# schematic.net
KiCad netlist of a schematic drawn in EasyEDA
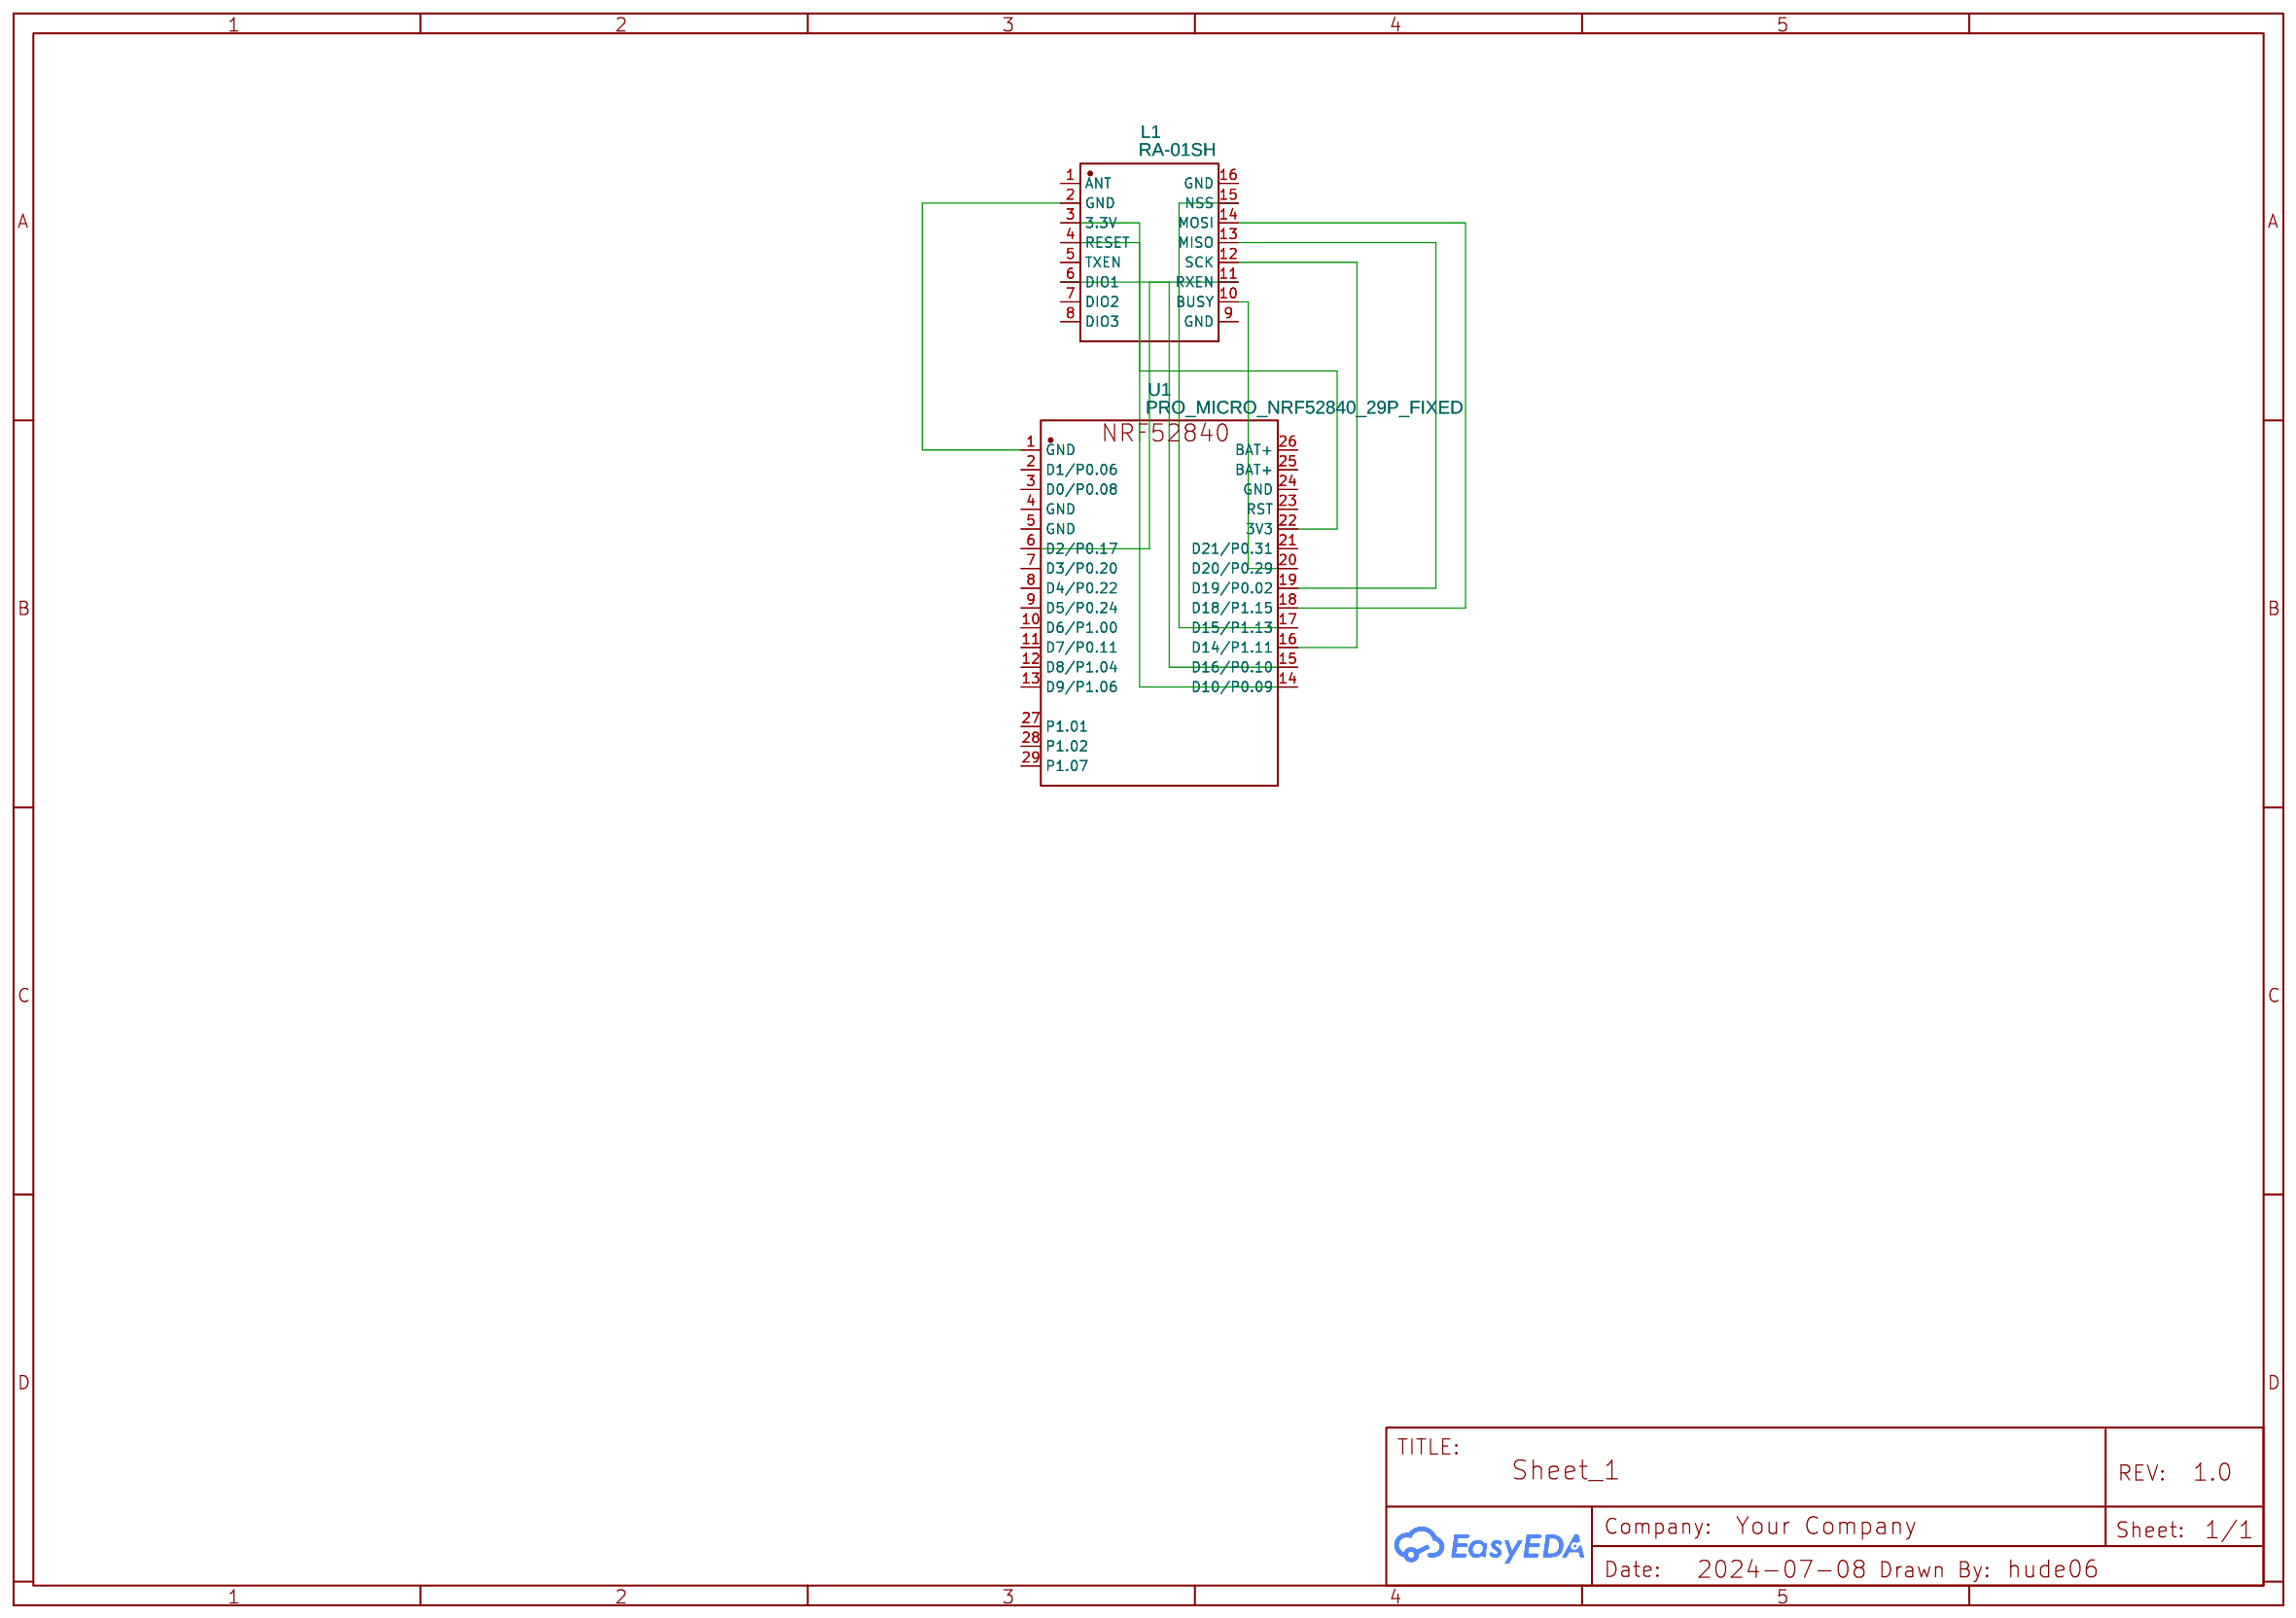
[diagram p0: schematic sheet]

(export (version "E")
  (design (tool "Eeschema 10.0.6"))
  (components
    (comp (ref "L1")
      (value "RA-01SH")
      (fields (field (name "Manufacturer Part") "Ra-01SH") (field (name "Manufacturer") "Ai-Thinker(安信可)"))
      (libsource (lib "") (part "RA-01SH"))
    )
    (comp (ref "U1")
      (value "PRO_MICRO_NRF52840_29P_FIXED")
      (libsource (lib "") (part "PRO_MICRO_NRF52840_29P_FIXED"))
    )
  )
  (nets
    (net (code "1") (name "Net-(L1-3.3V)") (class "Default")
      (node (ref "L1") (pin "3") (pinfunction "3.3V_3") (pintype "unspecified"))
      (node (ref "U1") (pin "22") (pinfunction "3V3_22") (pintype "unspecified"))
    )
    (net (code "2") (name "Net-(L1-BUSY)") (class "Default")
      (node (ref "L1") (pin "10") (pinfunction "BUSY_10") (pintype "unspecified"))
      (node (ref "U1") (pin "20") (pinfunction "D20/P0.29_20") (pintype "unspecified"))
    )
    (net (code "3") (name "Net-(L1-DIO1)") (class "Default")
      (node (ref "L1") (pin "6") (pinfunction "DIO1_6") (pintype "unspecified"))
      (node (ref "U1") (pin "15") (pinfunction "D16/P0.10_15") (pintype "unspecified"))
    )
    (net (code "4") (name "Net-(L1-GND-Pad2)") (class "Default")
      (node (ref "L1") (pin "2") (pinfunction "GND_2") (pintype "unspecified"))
      (node (ref "U1") (pin "1") (pinfunction "GND_1") (pintype "unspecified"))
    )
    (net (code "5") (name "Net-(L1-MISO)") (class "Default")
      (node (ref "L1") (pin "13") (pinfunction "MISO_13") (pintype "unspecified"))
      (node (ref "U1") (pin "19") (pinfunction "D19/P0.02_19") (pintype "unspecified"))
    )
    (net (code "6") (name "Net-(L1-MOSI)") (class "Default")
      (node (ref "L1") (pin "14") (pinfunction "MOSI_14") (pintype "unspecified"))
      (node (ref "U1") (pin "18") (pinfunction "D18/P1.15_18") (pintype "unspecified"))
    )
    (net (code "7") (name "Net-(L1-NSS)") (class "Default")
      (node (ref "L1") (pin "15") (pinfunction "NSS_15") (pintype "unspecified"))
      (node (ref "U1") (pin "17") (pinfunction "D15/P1.13_17") (pintype "unspecified"))
    )
    (net (code "8") (name "Net-(L1-RESET)") (class "Default")
      (node (ref "L1") (pin "4") (pinfunction "RESET_4") (pintype "unspecified"))
      (node (ref "U1") (pin "14") (pinfunction "D10/P0.09_14") (pintype "unspecified"))
    )
    (net (code "9") (name "Net-(L1-RXEN)") (class "Default")
      (node (ref "L1") (pin "11") (pinfunction "RXEN_11") (pintype "unspecified"))
      (node (ref "U1") (pin "6") (pinfunction "D2/P0.17_6") (pintype "unspecified"))
    )
    (net (code "10") (name "Net-(L1-SCK)") (class "Default")
      (node (ref "L1") (pin "12") (pinfunction "SCK_12") (pintype "unspecified"))
      (node (ref "U1") (pin "16") (pinfunction "D14/P1.11_16") (pintype "unspecified"))
    )
    (net (code "11") (name "unconnected-(L1-ANT-Pad1)") (class "Default")
      (node (ref "L1") (pin "1") (pinfunction "ANT_1") (pintype "unspecified"))
    )
    (net (code "12") (name "unconnected-(L1-DIO2-Pad7)") (class "Default")
      (node (ref "L1") (pin "7") (pinfunction "DIO2_7") (pintype "unspecified"))
    )
    (net (code "13") (name "unconnected-(L1-DIO3-Pad8)") (class "Default")
      (node (ref "L1") (pin "8") (pinfunction "DIO3_8") (pintype "unspecified"))
    )
    (net (code "14") (name "unconnected-(L1-GND-Pad9)") (class "Default")
      (node (ref "L1") (pin "9") (pinfunction "GND_9") (pintype "unspecified"))
    )
    (net (code "15") (name "unconnected-(L1-GND-Pad16)") (class "Default")
      (node (ref "L1") (pin "16") (pinfunction "GND_16") (pintype "unspecified"))
    )
    (net (code "16") (name "unconnected-(L1-TXEN-Pad5)") (class "Default")
      (node (ref "L1") (pin "5") (pinfunction "TXEN_5") (pintype "unspecified"))
    )
    (net (code "17") (name "unconnected-(U1-BAT+-Pad25)") (class "Default")
      (node (ref "U1") (pin "25") (pinfunction "BAT+_25") (pintype "unspecified"))
    )
    (net (code "18") (name "unconnected-(U1-BAT+-Pad26)") (class "Default")
      (node (ref "U1") (pin "26") (pinfunction "BAT+_26") (pintype "unspecified"))
    )
    (net (code "19") (name "unconnected-(U1-D0{slash}P0.08-Pad3)") (class "Default")
      (node (ref "U1") (pin "3") (pinfunction "D0/P0.08_3") (pintype "unspecified"))
    )
    (net (code "20") (name "unconnected-(U1-D1{slash}P0.06-Pad2)") (class "Default")
      (node (ref "U1") (pin "2") (pinfunction "D1/P0.06_2") (pintype "unspecified"))
    )
    (net (code "21") (name "unconnected-(U1-D3{slash}P0.20-Pad7)") (class "Default")
      (node (ref "U1") (pin "7") (pinfunction "D3/P0.20_7") (pintype "unspecified"))
    )
    (net (code "22") (name "unconnected-(U1-D4{slash}P0.22-Pad8)") (class "Default")
      (node (ref "U1") (pin "8") (pinfunction "D4/P0.22_8") (pintype "unspecified"))
    )
    (net (code "23") (name "unconnected-(U1-D5{slash}P0.24-Pad9)") (class "Default")
      (node (ref "U1") (pin "9") (pinfunction "D5/P0.24_9") (pintype "unspecified"))
    )
    (net (code "24") (name "unconnected-(U1-D6{slash}P1.00-Pad10)") (class "Default")
      (node (ref "U1") (pin "10") (pinfunction "D6/P1.00_10") (pintype "unspecified"))
    )
    (net (code "25") (name "unconnected-(U1-D7{slash}P0.11-Pad11)") (class "Default")
      (node (ref "U1") (pin "11") (pinfunction "D7/P0.11_11") (pintype "unspecified"))
    )
    (net (code "26") (name "unconnected-(U1-D8{slash}P1.04-Pad12)") (class "Default")
      (node (ref "U1") (pin "12") (pinfunction "D8/P1.04_12") (pintype "unspecified"))
    )
    (net (code "27") (name "unconnected-(U1-D9{slash}P1.06-Pad13)") (class "Default")
      (node (ref "U1") (pin "13") (pinfunction "D9/P1.06_13") (pintype "unspecified"))
    )
    (net (code "28") (name "unconnected-(U1-D21{slash}P0.31-Pad21)") (class "Default")
      (node (ref "U1") (pin "21") (pinfunction "D21/P0.31_21") (pintype "unspecified"))
    )
    (net (code "29") (name "unconnected-(U1-GND-Pad4)") (class "Default")
      (node (ref "U1") (pin "4") (pinfunction "GND_4") (pintype "unspecified"))
    )
    (net (code "30") (name "unconnected-(U1-GND-Pad5)") (class "Default")
      (node (ref "U1") (pin "5") (pinfunction "GND_5") (pintype "unspecified"))
    )
    (net (code "31") (name "unconnected-(U1-GND-Pad24)") (class "Default")
      (node (ref "U1") (pin "24") (pinfunction "GND_24") (pintype "unspecified"))
    )
    (net (code "32") (name "unconnected-(U1-P1.01-Pad27)") (class "Default")
      (node (ref "U1") (pin "27") (pinfunction "P1.01_27") (pintype "unspecified"))
    )
    (net (code "33") (name "unconnected-(U1-P1.02-Pad28)") (class "Default")
      (node (ref "U1") (pin "28") (pinfunction "P1.02_28") (pintype "unspecified"))
    )
    (net (code "34") (name "unconnected-(U1-P1.07-Pad29)") (class "Default")
      (node (ref "U1") (pin "29") (pinfunction "P1.07_29") (pintype "unspecified"))
    )
    (net (code "35") (name "unconnected-(U1-RST-Pad23)") (class "Default")
      (node (ref "U1") (pin "23") (pinfunction "RST_23") (pintype "unspecified"))
    )
  )
)
